# main.net
KiCad netlist of a schematic drawn in Altium Designer
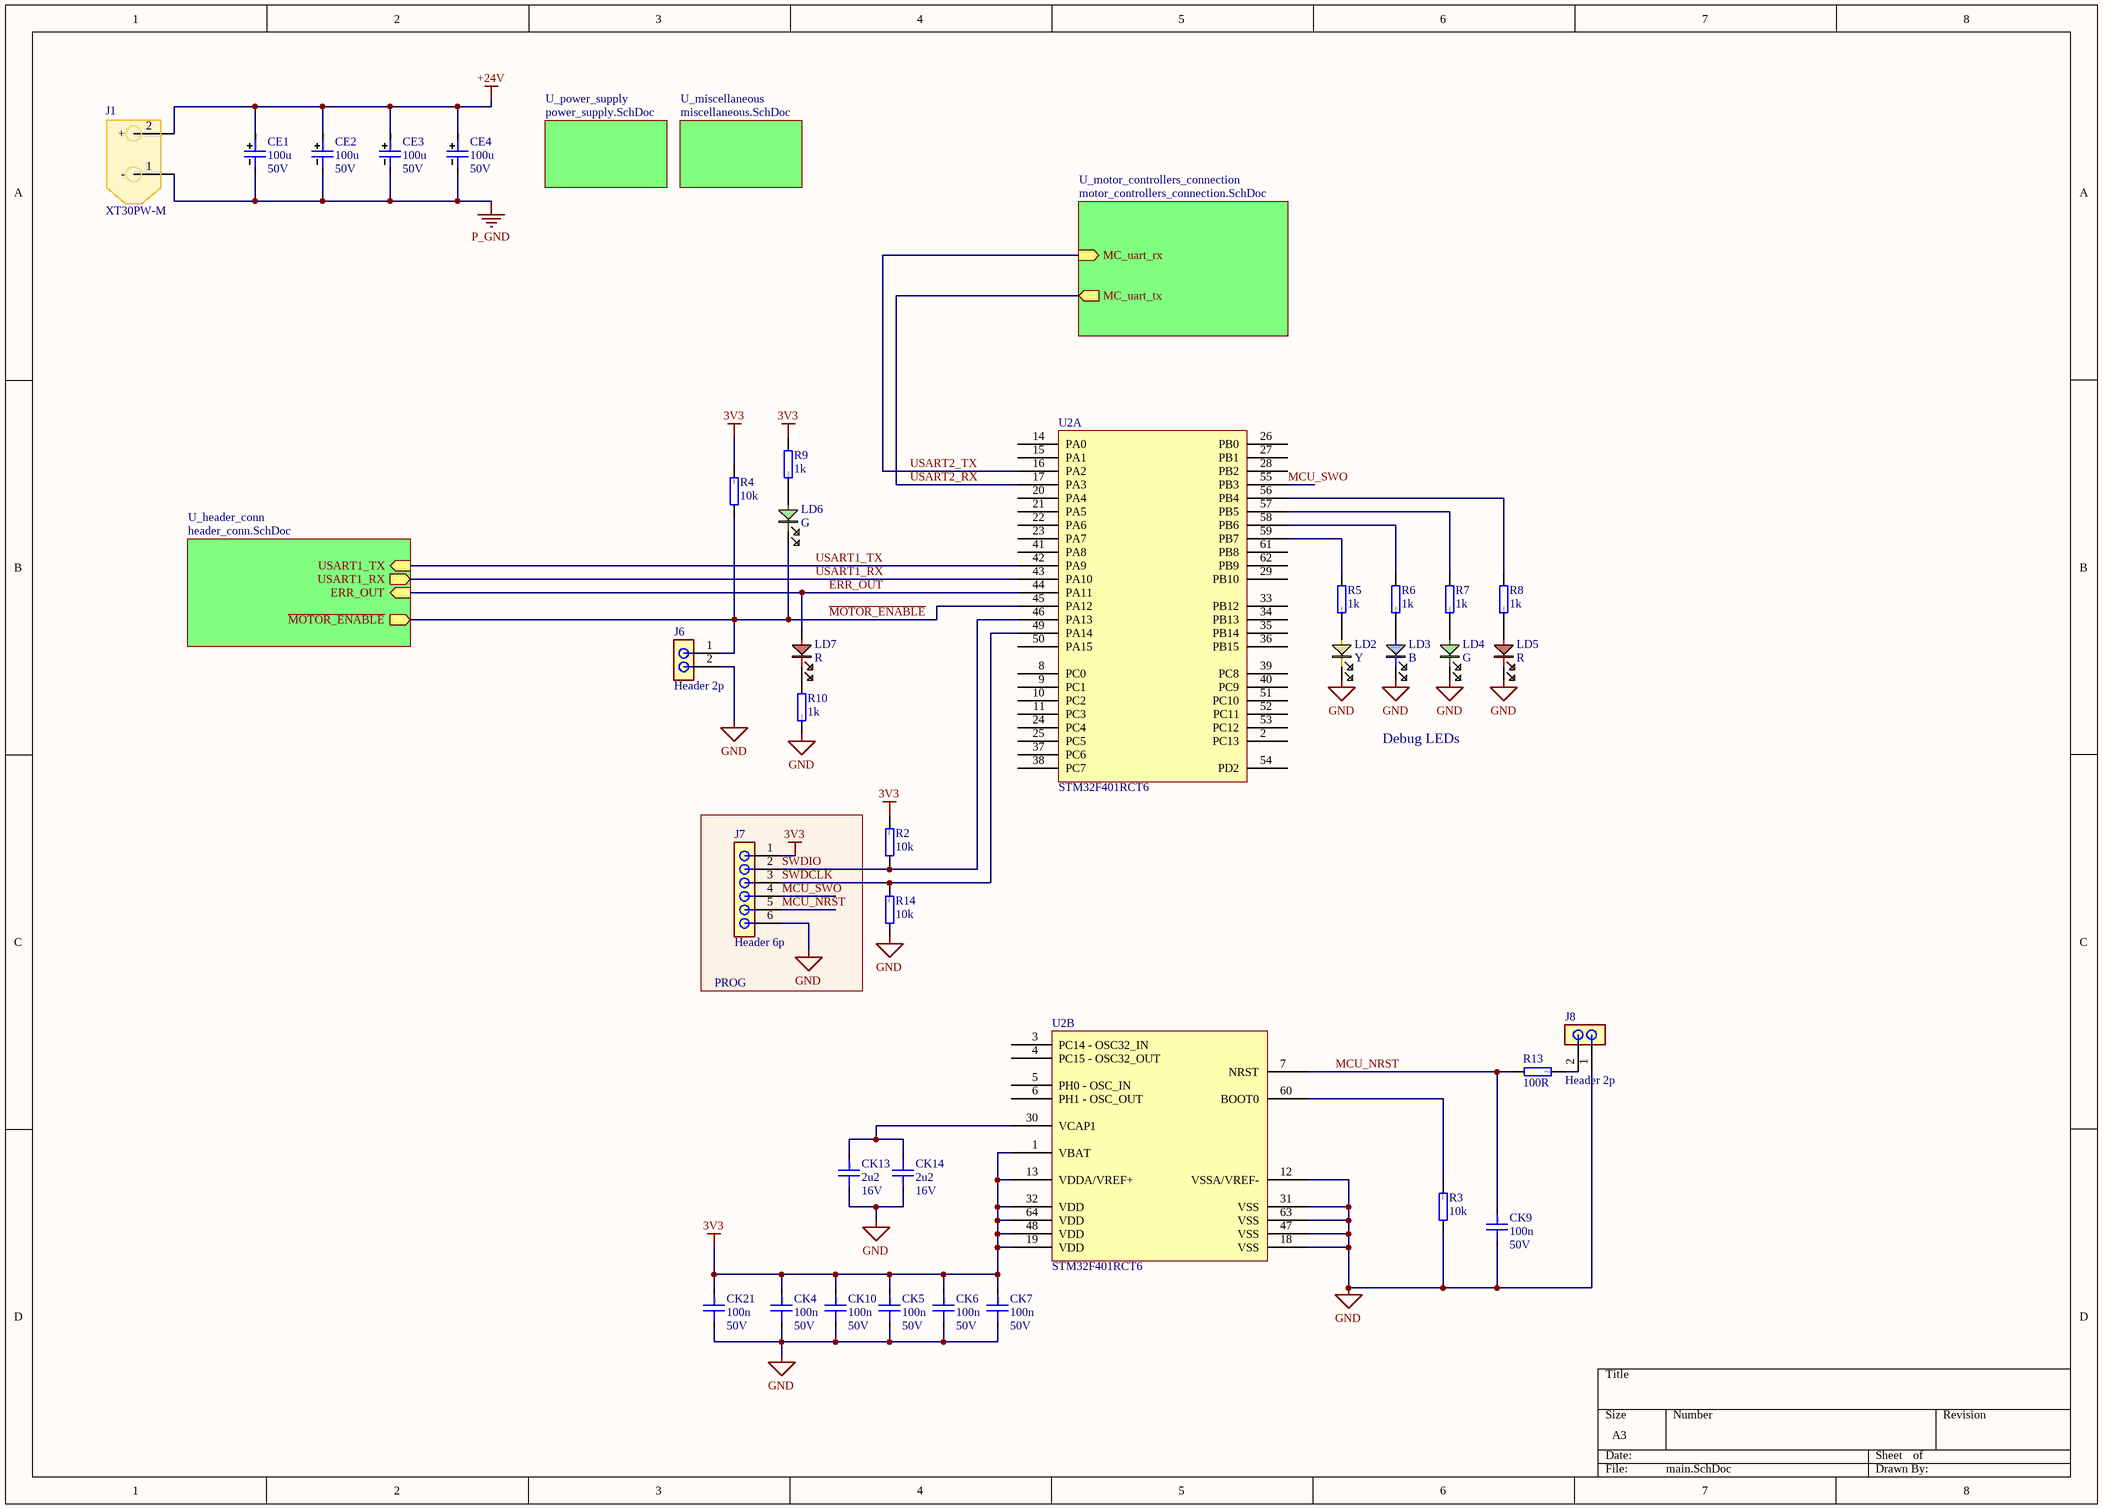
[diagram p0: main.SchDoc]

(export (version "E")
  (design (tool "Eeschema 10.0.6"))
  (components
    (comp (ref "CE1")
      (value "100u")
      (footprint "CAPAE830X1100N")
      (description "100uF 50V ±20% SMD,D8xL10.2mm Aluminum Electrolytic Capacitors - SMD ROHS")
      (fields
        (field (name "JLCPCB PART") "C3352")
        (field (name "TME PART") "CK1H107M08010VR")
        (field (name "VOLTAGE RATING") "50V")
      )
      (libsource (lib "Kubikova ultra knihovna") (part "Cap el 100u 50V"))
    )
    (comp (ref "CE2")
      (value "100u")
      (footprint "CAPAE830X1100N")
      (description "100uF 50V ±20% SMD,D8xL10.2mm Aluminum Electrolytic Capacitors - SMD ROHS")
      (fields
        (field (name "JLCPCB PART") "C3352")
        (field (name "TME PART") "CK1H107M08010VR")
        (field (name "VOLTAGE RATING") "50V")
      )
      (libsource (lib "Kubikova ultra knihovna") (part "Cap el 100u 50V"))
    )
    (comp (ref "CE3")
      (value "100u")
      (footprint "CAPAE830X1100N")
      (description "100uF 50V ±20% SMD,D8xL10.2mm Aluminum Electrolytic Capacitors - SMD ROHS")
      (fields
        (field (name "JLCPCB PART") "C3352")
        (field (name "TME PART") "CK1H107M08010VR")
        (field (name "VOLTAGE RATING") "50V")
      )
      (libsource (lib "Kubikova ultra knihovna") (part "Cap el 100u 50V"))
    )
    (comp (ref "CE4")
      (value "100u")
      (footprint "CAPAE830X1100N")
      (description "100uF 50V ±20% SMD,D8xL10.2mm Aluminum Electrolytic Capacitors - SMD ROHS")
      (fields
        (field (name "JLCPCB PART") "C3352")
        (field (name "TME PART") "CK1H107M08010VR")
        (field (name "VOLTAGE RATING") "50V")
      )
      (libsource (lib "Kubikova ultra knihovna") (part "Cap el 100u 50V"))
    )
    (comp (ref "CK4")
      (value "100n")
      (footprint "CAP0603")
      (description "50V 100nF X7R ±10% 0603 Multilayer Ceramic Capacitors MLCC - SMD/SMT ROHS")
      (fields (field (name "JLCPCB PART") "C14663") (field (name "VOLTAGE RATING") "50V"))
      (libsource (lib "Kubikova ultra knihovna") (part "Cap 100n 0603"))
    )
    (comp (ref "CK5")
      (value "100n")
      (footprint "CAP0603")
      (description "50V 100nF X7R ±10% 0603 Multilayer Ceramic Capacitors MLCC - SMD/SMT ROHS")
      (fields (field (name "JLCPCB PART") "C14663") (field (name "VOLTAGE RATING") "50V"))
      (libsource (lib "Kubikova ultra knihovna") (part "Cap 100n 0603"))
    )
    (comp (ref "CK6")
      (value "100n")
      (footprint "CAP0603")
      (description "50V 100nF X7R ±10% 0603 Multilayer Ceramic Capacitors MLCC - SMD/SMT ROHS")
      (fields (field (name "JLCPCB PART") "C14663") (field (name "VOLTAGE RATING") "50V"))
      (libsource (lib "Kubikova ultra knihovna") (part "Cap 100n 0603"))
    )
    (comp (ref "CK7")
      (value "100n")
      (footprint "CAP0603")
      (description "50V 100nF X7R ±10% 0603 Multilayer Ceramic Capacitors MLCC - SMD/SMT ROHS")
      (fields (field (name "JLCPCB PART") "C14663") (field (name "VOLTAGE RATING") "50V"))
      (libsource (lib "Kubikova ultra knihovna") (part "Cap 100n 0603"))
    )
    (comp (ref "CK9")
      (value "100n")
      (footprint "CAP0603")
      (description "50V 100nF X7R ±10% 0603 Multilayer Ceramic Capacitors MLCC - SMD/SMT ROHS")
      (fields (field (name "JLCPCB PART") "C14663") (field (name "VOLTAGE RATING") "50V"))
      (libsource (lib "Kubikova ultra knihovna") (part "Cap 100n 0603"))
    )
    (comp (ref "CK10")
      (value "100n")
      (footprint "CAP0603")
      (description "50V 100nF X7R ±10% 0603 Multilayer Ceramic Capacitors MLCC - SMD/SMT ROHS")
      (fields (field (name "JLCPCB PART") "C14663") (field (name "VOLTAGE RATING") "50V"))
      (libsource (lib "Kubikova ultra knihovna") (part "Cap 100n 0603"))
    )
    (comp (ref "CK13")
      (value "2u2")
      (footprint "CAP0603")
      (description "16V 2.2uF X5R ±10% 0603 Multilayer Ceramic Capacitors MLCC - SMD/SMT ROHS")
      (fields (field (name "JLCPCB PART") "C23630") (field (name "VOLTAGE RATING") "16V"))
      (libsource (lib "Kubikova ultra knihovna") (part "Cap 2u2 0603"))
    )
    (comp (ref "CK14")
      (value "2u2")
      (footprint "CAP0603")
      (description "16V 2.2uF X5R ±10% 0603 Multilayer Ceramic Capacitors MLCC - SMD/SMT ROHS")
      (fields (field (name "JLCPCB PART") "C23630") (field (name "VOLTAGE RATING") "16V"))
      (libsource (lib "Kubikova ultra knihovna") (part "Cap 2u2 0603"))
    )
    (comp (ref "CK21")
      (value "100n")
      (footprint "CAP0603")
      (description "50V 100nF X7R ±10% 0603 Multilayer Ceramic Capacitors MLCC - SMD/SMT ROHS")
      (fields (field (name "JLCPCB PART") "C14663") (field (name "VOLTAGE RATING") "50V"))
      (libsource (lib "Kubikova ultra knihovna") (part "Cap 100n 0603"))
    )
    (comp (ref "J1")
      (value "XT30PW-M")
      (footprint "XT30PWM")
      (description "plug")
      (fields (field (name "JLCPCB PART") "C431092"))
      (libsource (lib "Kubikova ultra knihovna") (part "XT30 male"))
    )
    (comp (ref "J6")
      (value "Header 2p")
      (footprint "Pin header 2p")
      (description "Connector")
      (fields
        (field (name "MANUFACTURER_PART_NUMBER") "DS1021-1*2SF11-B")
        (field (name "JLCPCB PART") "C492401")
      )
      (libsource (lib "Kubikova ultra knihovna") (part "Pin header 2p"))
    )
    (comp (ref "J7")
      (value "Header 6p")
      (footprint "Pin header 6p")
      (fields
        (field (name "MANUFACTURER_PART_NUMBER") "DS1021-1*2SF11-B")
        (field (name "JLCPCB PART") "C37208")
      )
      (libsource (lib "Kubikova ultra knihovna") (part "Pin header 6p"))
    )
    (comp (ref "J8")
      (value "Header 2p")
      (footprint "Pin header 2p")
      (description "Connector")
      (fields
        (field (name "MANUFACTURER_PART_NUMBER") "DS1021-1*2SF11-B")
        (field (name "JLCPCB PART") "C492401")
      )
      (libsource (lib "") (part "Pin header 2p_1"))
    )
    (comp (ref "LD2")
      (value "Y")
      (footprint "0603_LED_Y")
      (description "0603 Yellow Led")
      (fields (field (name "JLCPCB PART") "C7496811"))
      (libsource (lib "Kubikova ultra knihovna") (part "LED Y 0603"))
    )
    (comp (ref "LD3")
      (value "B")
      (footprint "0603_LED_B")
      (description "0603 Blue Led")
      (fields (field (name "JLCPCB PART") "C7496819"))
      (libsource (lib "Kubikova ultra knihovna") (part "LED B 0603"))
    )
    (comp (ref "LD4")
      (value "G")
      (footprint "0603_LED_G")
      (description "0603 Green Led")
      (fields (field (name "JLCPCB PART") "C22371297"))
      (libsource (lib "Kubikova ultra knihovna") (part "LED G 0603"))
    )
    (comp (ref "LD5")
      (value "R")
      (footprint "0603_LED_R")
      (description "-40℃~+85℃ Red 0603 LED Indication - Discrete ROHS")
      (fields (field (name "JLCPCB PART") "C2286"))
      (libsource (lib "Kubikova ultra knihovna") (part "LED R 0603"))
    )
    (comp (ref "LD6")
      (value "G")
      (footprint "0603_LED_G")
      (description "0603 Green Led")
      (fields (field (name "JLCPCB PART") "C22371297"))
      (libsource (lib "Kubikova ultra knihovna") (part "LED G 0603"))
    )
    (comp (ref "LD7")
      (value "R")
      (footprint "0603_LED_R")
      (description "-40℃~+85℃ Red 0603 LED Indication - Discrete ROHS")
      (fields (field (name "JLCPCB PART") "C2286"))
      (libsource (lib "Kubikova ultra knihovna") (part "LED R 0603"))
    )
    (comp (ref "R2")
      (value "10k")
      (footprint "RESC2012X06N(SMR0805)")
      (description "125mW Thick Film Resistors 150V ±100ppm/℃ ±1% 10kΩ 0805 Chip Resistor - Surface Mount ROHS")
      (fields (field (name "JLCPCB PART") "C17414"))
      (libsource (lib "Kubikova ultra knihovna") (part "Res 10k 0805"))
    )
    (comp (ref "R3")
      (value "10k")
      (footprint "RESC2012X06N(SMR0805)")
      (description "125mW Thick Film Resistors 150V ±100ppm/℃ ±1% 10kΩ 0805 Chip Resistor - Surface Mount ROHS")
      (fields (field (name "JLCPCB PART") "C17414"))
      (libsource (lib "Kubikova ultra knihovna") (part "Res 10k 0805"))
    )
    (comp (ref "R4")
      (value "10k")
      (footprint "RESC2012X06N(SMR0805)")
      (description "125mW Thick Film Resistors 150V ±100ppm/℃ ±1% 10kΩ 0805 Chip Resistor - Surface Mount ROHS")
      (fields (field (name "JLCPCB PART") "C17414"))
      (libsource (lib "Kubikova ultra knihovna") (part "Res 10k 0805"))
    )
    (comp (ref "R5")
      (value "1k")
      (footprint "RESC2012X06N(SMR0805)")
      (description "125mW Thick Film Resistors 150V ±100ppm/℃ ±1% 1kΩ 0805 Chip Resistor - Surface Mount ROHS")
      (fields (field (name "JLCPCB PART") "C17513") (field (name "AUTHOR") "JP/27.03.2014"))
      (libsource (lib "Kubikova ultra knihovna") (part "Res 1k 0805"))
    )
    (comp (ref "R6")
      (value "1k")
      (footprint "RESC2012X06N(SMR0805)")
      (description "125mW Thick Film Resistors 150V ±100ppm/℃ ±1% 1kΩ 0805 Chip Resistor - Surface Mount ROHS")
      (fields (field (name "JLCPCB PART") "C17513") (field (name "AUTHOR") "JP/27.03.2014"))
      (libsource (lib "Kubikova ultra knihovna") (part "Res 1k 0805"))
    )
    (comp (ref "R7")
      (value "1k")
      (footprint "RESC2012X06N(SMR0805)")
      (description "125mW Thick Film Resistors 150V ±100ppm/℃ ±1% 1kΩ 0805 Chip Resistor - Surface Mount ROHS")
      (fields (field (name "JLCPCB PART") "C17513") (field (name "AUTHOR") "JP/27.03.2014"))
      (libsource (lib "Kubikova ultra knihovna") (part "Res 1k 0805"))
    )
    (comp (ref "R8")
      (value "1k")
      (footprint "RESC2012X06N(SMR0805)")
      (description "125mW Thick Film Resistors 150V ±100ppm/℃ ±1% 1kΩ 0805 Chip Resistor - Surface Mount ROHS")
      (fields (field (name "JLCPCB PART") "C17513") (field (name "AUTHOR") "JP/27.03.2014"))
      (libsource (lib "Kubikova ultra knihovna") (part "Res 1k 0805"))
    )
    (comp (ref "R9")
      (value "1k")
      (footprint "RESC2012X06N(SMR0805)")
      (description "125mW Thick Film Resistors 150V ±100ppm/℃ ±1% 1kΩ 0805 Chip Resistor - Surface Mount ROHS")
      (fields (field (name "JLCPCB PART") "C17513") (field (name "AUTHOR") "JP/27.03.2014"))
      (libsource (lib "Kubikova ultra knihovna") (part "Res 1k 0805"))
    )
    (comp (ref "R10")
      (value "1k")
      (footprint "RESC2012X06N(SMR0805)")
      (description "125mW Thick Film Resistors 150V ±100ppm/℃ ±1% 1kΩ 0805 Chip Resistor - Surface Mount ROHS")
      (fields (field (name "JLCPCB PART") "C17513") (field (name "AUTHOR") "JP/27.03.2014"))
      (libsource (lib "Kubikova ultra knihovna") (part "Res 1k 0805"))
    )
    (comp (ref "R13")
      (value "100R")
      (footprint "RESC2012X06N(SMR0805)")
      (description "125mW Thick Film Resistors 150V ±100ppm/℃ ±1% 100Ω 0805 Chip Resistor - Surface Mount ROHS")
      (fields (field (name "JLCPCB PART") "C17408") (field (name "AUTHOR") "JP/27.03.2014"))
      (libsource (lib "Kubikova ultra knihovna") (part "Res 100R 0805"))
    )
    (comp (ref "R14")
      (value "10k")
      (footprint "RESC2012X06N(SMR0805)")
      (description "125mW Thick Film Resistors 150V ±100ppm/℃ ±1% 10kΩ 0805 Chip Resistor - Surface Mount ROHS")
      (fields (field (name "JLCPCB PART") "C17414"))
      (libsource (lib "Kubikova ultra knihovna") (part "Res 10k 0805"))
    )
    (comp (ref "U2")
      (value "STM32F401RCT6")
      (footprint "LQFP64")
      (description "256KB 1.7V~3.6V ARM-M4 64KB 84MHz FLASH 50 LQFP-64(10x10) Microcontrollers (MCU/MPU/SOC) ROHS")
      (fields (field (name "JLCPCB PART") "C74524"))
      (libsource (lib "Kubikova ultra knihovna") (part "STM32F401RCT6"))
    )
  )
  (nets
    (net (code "1") (name "+24V") (class "Default")
      (node (ref "CE1") (pin "1") (pinfunction "1_1") (pintype "passive"))
      (node (ref "CE2") (pin "1") (pinfunction "1_1") (pintype "passive"))
      (node (ref "CE3") (pin "1") (pinfunction "1_1") (pintype "passive"))
      (node (ref "CE4") (pin "1") (pinfunction "1_1") (pintype "passive"))
      (node (ref "J1") (pin "2") (pinfunction "+_2") (pintype "passive"))
    )
    (net (code "2") (name "/ERR_OUT") (class "Default")
      (node (ref "LD7") (pin "1") (pintype "passive"))
      (node (ref "U2") (pin "44") (pinfunction "PA11_44") (pintype "passive"))
    )
    (net (code "3") (name "/MCU_NRST") (class "Default")
      (node (ref "CK9") (pin "1") (pinfunction "1_1") (pintype "passive"))
      (node (ref "J7") (pin "5") (pinfunction "5_5") (pintype "passive"))
      (node (ref "R13") (pin "1") (pinfunction "1_1") (pintype "passive"))
      (node (ref "U2") (pin "7") (pinfunction "NRST_7") (pintype "passive"))
    )
    (net (code "4") (name "/MCU_SWO") (class "Default")
      (node (ref "J7") (pin "4") (pinfunction "4_4") (pintype "passive"))
      (node (ref "U2") (pin "55") (pinfunction "PB3_55") (pintype "passive"))
    )
    (net (code "5") (name "/SWDCLK") (class "Default")
      (node (ref "J7") (pin "3") (pinfunction "3_3") (pintype "passive"))
      (node (ref "R14") (pin "2") (pinfunction "2_2") (pintype "passive"))
      (node (ref "U2") (pin "49") (pinfunction "PA14_49") (pintype "passive"))
    )
    (net (code "6") (name "/SWDIO") (class "Default")
      (node (ref "J7") (pin "2") (pinfunction "2_2") (pintype "passive"))
      (node (ref "R2") (pin "1") (pinfunction "1_1") (pintype "passive"))
      (node (ref "U2") (pin "46") (pinfunction "PA13_46") (pintype "passive"))
    )
    (net (code "7") (name "/USART1_RX") (class "Default")
      (node (ref "U2") (pin "43") (pinfunction "PA10_43") (pintype "passive"))
    )
    (net (code "8") (name "/USART1_TX") (class "Default")
      (node (ref "U2") (pin "42") (pinfunction "PA9_42") (pintype "passive"))
    )
    (net (code "9") (name "/USART2_RX") (class "Default")
      (node (ref "U2") (pin "17") (pinfunction "PA3_17") (pintype "passive"))
    )
    (net (code "10") (name "/USART2_TX") (class "Default")
      (node (ref "U2") (pin "16") (pinfunction "PA2_16") (pintype "passive"))
    )
    (net (code "11") (name "/~{MOTOR_ENABLE}") (class "Default")
      (node (ref "J6") (pin "1") (pinfunction "1_1") (pintype "passive"))
      (node (ref "LD6") (pin "2") (pintype "passive"))
      (node (ref "R4") (pin "1") (pinfunction "1_1") (pintype "passive"))
      (node (ref "U2") (pin "45") (pinfunction "PA12_45") (pintype "passive"))
    )
    (net (code "12") (name "3V3") (class "Default")
      (node (ref "CK10") (pin "1") (pinfunction "1_1") (pintype "passive"))
      (node (ref "CK21") (pin "1") (pinfunction "1_1") (pintype "passive"))
      (node (ref "CK4") (pin "1") (pinfunction "1_1") (pintype "passive"))
      (node (ref "CK5") (pin "1") (pinfunction "1_1") (pintype "passive"))
      (node (ref "CK6") (pin "1") (pinfunction "1_1") (pintype "passive"))
      (node (ref "CK7") (pin "1") (pinfunction "1_1") (pintype "passive"))
      (node (ref "J7") (pin "1") (pinfunction "1_1") (pintype "passive"))
      (node (ref "R2") (pin "2") (pinfunction "2_2") (pintype "passive"))
      (node (ref "R4") (pin "2") (pinfunction "2_2") (pintype "passive"))
      (node (ref "R9") (pin "1") (pinfunction "1_1") (pintype "passive"))
      (node (ref "U2") (pin "1") (pinfunction "VBAT_1") (pintype "passive"))
      (node (ref "U2") (pin "13") (pinfunction "VDDA/VREF+_13") (pintype "passive"))
      (node (ref "U2") (pin "19") (pinfunction "VDD_19") (pintype "passive"))
      (node (ref "U2") (pin "32") (pinfunction "VDD_32") (pintype "passive"))
      (node (ref "U2") (pin "48") (pinfunction "VDD_48") (pintype "passive"))
      (node (ref "U2") (pin "64") (pinfunction "VDD_64") (pintype "passive"))
    )
    (net (code "13") (name "GND") (class "Default")
      (node (ref "CK10") (pin "2") (pinfunction "2_2") (pintype "passive"))
      (node (ref "CK13") (pin "2") (pinfunction "2_2") (pintype "passive"))
      (node (ref "CK14") (pin "1") (pinfunction "1_1") (pintype "passive"))
      (node (ref "CK21") (pin "2") (pinfunction "2_2") (pintype "passive"))
      (node (ref "CK4") (pin "2") (pinfunction "2_2") (pintype "passive"))
      (node (ref "CK5") (pin "2") (pinfunction "2_2") (pintype "passive"))
      (node (ref "CK6") (pin "2") (pinfunction "2_2") (pintype "passive"))
      (node (ref "CK7") (pin "2") (pinfunction "2_2") (pintype "passive"))
      (node (ref "CK9") (pin "2") (pinfunction "2_2") (pintype "passive"))
      (node (ref "J6") (pin "2") (pinfunction "2_2") (pintype "passive"))
      (node (ref "J7") (pin "6") (pinfunction "6_6") (pintype "passive"))
      (node (ref "J8") (pin "1") (pinfunction "1_1") (pintype "passive"))
      (node (ref "LD2") (pin "2") (pintype "passive"))
      (node (ref "LD3") (pin "2") (pintype "passive"))
      (node (ref "LD4") (pin "2") (pintype "passive"))
      (node (ref "LD5") (pin "2") (pintype "passive"))
      (node (ref "R10") (pin "2") (pinfunction "2_2") (pintype "passive"))
      (node (ref "R14") (pin "1") (pinfunction "1_1") (pintype "passive"))
      (node (ref "R3") (pin "1") (pinfunction "1_1") (pintype "passive"))
      (node (ref "U2") (pin "12") (pinfunction "VSSA/VREF-_12") (pintype "passive"))
      (node (ref "U2") (pin "18") (pinfunction "VSS_18") (pintype "passive"))
      (node (ref "U2") (pin "31") (pinfunction "VSS_31") (pintype "passive"))
      (node (ref "U2") (pin "47") (pinfunction "VSS_47") (pintype "passive"))
      (node (ref "U2") (pin "63") (pinfunction "VSS_63") (pintype "passive"))
    )
    (net (code "14") (name "Net-(J8-Pad2)") (class "Default")
      (node (ref "J8") (pin "2") (pinfunction "2_2") (pintype "passive"))
      (node (ref "R13") (pin "2") (pinfunction "2_2") (pintype "passive"))
    )
    (net (code "15") (name "Net-(LD2-Pad1)") (class "Default")
      (node (ref "LD2") (pin "1") (pintype "passive"))
      (node (ref "R5") (pin "2") (pinfunction "2_2") (pintype "passive"))
    )
    (net (code "16") (name "Net-(LD3-Pad1)") (class "Default")
      (node (ref "LD3") (pin "1") (pintype "passive"))
      (node (ref "R6") (pin "2") (pinfunction "2_2") (pintype "passive"))
    )
    (net (code "17") (name "Net-(LD4-Pad1)") (class "Default")
      (node (ref "LD4") (pin "1") (pintype "passive"))
      (node (ref "R7") (pin "2") (pinfunction "2_2") (pintype "passive"))
    )
    (net (code "18") (name "Net-(LD5-Pad1)") (class "Default")
      (node (ref "LD5") (pin "1") (pintype "passive"))
      (node (ref "R8") (pin "2") (pinfunction "2_2") (pintype "passive"))
    )
    (net (code "19") (name "Net-(LD6-Pad1)") (class "Default")
      (node (ref "LD6") (pin "1") (pintype "passive"))
      (node (ref "R9") (pin "2") (pinfunction "2_2") (pintype "passive"))
    )
    (net (code "20") (name "Net-(LD7-Pad2)") (class "Default")
      (node (ref "LD7") (pin "2") (pintype "passive"))
      (node (ref "R10") (pin "1") (pinfunction "1_1") (pintype "passive"))
    )
    (net (code "21") (name "Net-(U2A-PB4)") (class "Default")
      (node (ref "R8") (pin "1") (pinfunction "1_1") (pintype "passive"))
      (node (ref "U2") (pin "56") (pinfunction "PB4_56") (pintype "passive"))
    )
    (net (code "22") (name "Net-(U2A-PB5)") (class "Default")
      (node (ref "R7") (pin "1") (pinfunction "1_1") (pintype "passive"))
      (node (ref "U2") (pin "57") (pinfunction "PB5_57") (pintype "passive"))
    )
    (net (code "23") (name "Net-(U2A-PB6)") (class "Default")
      (node (ref "R6") (pin "1") (pinfunction "1_1") (pintype "passive"))
      (node (ref "U2") (pin "58") (pinfunction "PB6_58") (pintype "passive"))
    )
    (net (code "24") (name "Net-(U2A-PB7)") (class "Default")
      (node (ref "R5") (pin "1") (pinfunction "1_1") (pintype "passive"))
      (node (ref "U2") (pin "59") (pinfunction "PB7_59") (pintype "passive"))
    )
    (net (code "25") (name "Net-(U2B-BOOT0)") (class "Default")
      (node (ref "R3") (pin "2") (pinfunction "2_2") (pintype "passive"))
      (node (ref "U2") (pin "60") (pinfunction "BOOT0_60") (pintype "passive"))
    )
    (net (code "26") (name "Net-(U2B-VCAP1)") (class "Default")
      (node (ref "CK13") (pin "1") (pinfunction "1_1") (pintype "passive"))
      (node (ref "CK14") (pin "2") (pinfunction "2_2") (pintype "passive"))
      (node (ref "U2") (pin "30") (pinfunction "VCAP1_30") (pintype "passive"))
    )
    (net (code "27") (name "P_GND") (class "Default")
      (node (ref "CE1") (pin "2") (pinfunction "2_2") (pintype "passive"))
      (node (ref "CE2") (pin "2") (pinfunction "2_2") (pintype "passive"))
      (node (ref "CE3") (pin "2") (pinfunction "2_2") (pintype "passive"))
      (node (ref "CE4") (pin "2") (pinfunction "2_2") (pintype "passive"))
      (node (ref "J1") (pin "1") (pinfunction "-_1") (pintype "passive"))
    )
    (net (code "28") (name "unconnected-(U2A-PA0-Pad14)") (class "Default")
      (node (ref "U2") (pin "14") (pinfunction "PA0_14") (pintype "passive"))
    )
    (net (code "29") (name "unconnected-(U2A-PA1-Pad15)") (class "Default")
      (node (ref "U2") (pin "15") (pinfunction "PA1_15") (pintype "passive"))
    )
    (net (code "30") (name "unconnected-(U2A-PA4-Pad20)") (class "Default")
      (node (ref "U2") (pin "20") (pinfunction "PA4_20") (pintype "passive"))
    )
    (net (code "31") (name "unconnected-(U2A-PA5-Pad21)") (class "Default")
      (node (ref "U2") (pin "21") (pinfunction "PA5_21") (pintype "passive"))
    )
    (net (code "32") (name "unconnected-(U2A-PA6-Pad22)") (class "Default")
      (node (ref "U2") (pin "22") (pinfunction "PA6_22") (pintype "passive"))
    )
    (net (code "33") (name "unconnected-(U2A-PA7-Pad23)") (class "Default")
      (node (ref "U2") (pin "23") (pinfunction "PA7_23") (pintype "passive"))
    )
    (net (code "34") (name "unconnected-(U2A-PA8-Pad41)") (class "Default")
      (node (ref "U2") (pin "41") (pinfunction "PA8_41") (pintype "passive"))
    )
    (net (code "35") (name "unconnected-(U2A-PA15-Pad50)") (class "Default")
      (node (ref "U2") (pin "50") (pinfunction "PA15_50") (pintype "passive"))
    )
    (net (code "36") (name "unconnected-(U2A-PB0-Pad26)") (class "Default")
      (node (ref "U2") (pin "26") (pinfunction "PB0_26") (pintype "passive"))
    )
    (net (code "37") (name "unconnected-(U2A-PB1-Pad27)") (class "Default")
      (node (ref "U2") (pin "27") (pinfunction "PB1_27") (pintype "passive"))
    )
    (net (code "38") (name "unconnected-(U2A-PB2-Pad28)") (class "Default")
      (node (ref "U2") (pin "28") (pinfunction "PB2_28") (pintype "passive"))
    )
    (net (code "39") (name "unconnected-(U2A-PB8-Pad61)") (class "Default")
      (node (ref "U2") (pin "61") (pinfunction "PB8_61") (pintype "passive"))
    )
    (net (code "40") (name "unconnected-(U2A-PB9-Pad62)") (class "Default")
      (node (ref "U2") (pin "62") (pinfunction "PB9_62") (pintype "passive"))
    )
    (net (code "41") (name "unconnected-(U2A-PB10-Pad29)") (class "Default")
      (node (ref "U2") (pin "29") (pinfunction "PB10_29") (pintype "passive"))
    )
    (net (code "42") (name "unconnected-(U2A-PB12-Pad33)") (class "Default")
      (node (ref "U2") (pin "33") (pinfunction "PB12_33") (pintype "passive"))
    )
    (net (code "43") (name "unconnected-(U2A-PB13-Pad34)") (class "Default")
      (node (ref "U2") (pin "34") (pinfunction "PB13_34") (pintype "passive"))
    )
    (net (code "44") (name "unconnected-(U2A-PB14-Pad35)") (class "Default")
      (node (ref "U2") (pin "35") (pinfunction "PB14_35") (pintype "passive"))
    )
    (net (code "45") (name "unconnected-(U2A-PB15-Pad36)") (class "Default")
      (node (ref "U2") (pin "36") (pinfunction "PB15_36") (pintype "passive"))
    )
    (net (code "46") (name "unconnected-(U2A-PC0-Pad8)") (class "Default")
      (node (ref "U2") (pin "8") (pinfunction "PC0_8") (pintype "passive"))
    )
    (net (code "47") (name "unconnected-(U2A-PC1-Pad9)") (class "Default")
      (node (ref "U2") (pin "9") (pinfunction "PC1_9") (pintype "passive"))
    )
    (net (code "48") (name "unconnected-(U2A-PC2-Pad10)") (class "Default")
      (node (ref "U2") (pin "10") (pinfunction "PC2_10") (pintype "passive"))
    )
    (net (code "49") (name "unconnected-(U2A-PC3-Pad11)") (class "Default")
      (node (ref "U2") (pin "11") (pinfunction "PC3_11") (pintype "passive"))
    )
    (net (code "50") (name "unconnected-(U2A-PC4-Pad24)") (class "Default")
      (node (ref "U2") (pin "24") (pinfunction "PC4_24") (pintype "passive"))
    )
    (net (code "51") (name "unconnected-(U2A-PC5-Pad25)") (class "Default")
      (node (ref "U2") (pin "25") (pinfunction "PC5_25") (pintype "passive"))
    )
    (net (code "52") (name "unconnected-(U2A-PC6-Pad37)") (class "Default")
      (node (ref "U2") (pin "37") (pinfunction "PC6_37") (pintype "passive"))
    )
    (net (code "53") (name "unconnected-(U2A-PC7-Pad38)") (class "Default")
      (node (ref "U2") (pin "38") (pinfunction "PC7_38") (pintype "passive"))
    )
    (net (code "54") (name "unconnected-(U2A-PC8-Pad39)") (class "Default")
      (node (ref "U2") (pin "39") (pinfunction "PC8_39") (pintype "passive"))
    )
    (net (code "55") (name "unconnected-(U2A-PC9-Pad40)") (class "Default")
      (node (ref "U2") (pin "40") (pinfunction "PC9_40") (pintype "passive"))
    )
    (net (code "56") (name "unconnected-(U2A-PC10-Pad51)") (class "Default")
      (node (ref "U2") (pin "51") (pinfunction "PC10_51") (pintype "passive"))
    )
    (net (code "57") (name "unconnected-(U2A-PC11-Pad52)") (class "Default")
      (node (ref "U2") (pin "52") (pinfunction "PC11_52") (pintype "passive"))
    )
    (net (code "58") (name "unconnected-(U2A-PC12-Pad53)") (class "Default")
      (node (ref "U2") (pin "53") (pinfunction "PC12_53") (pintype "passive"))
    )
    (net (code "59") (name "unconnected-(U2A-PC13-Pad2)") (class "Default")
      (node (ref "U2") (pin "2") (pinfunction "PC13_2") (pintype "passive"))
    )
    (net (code "60") (name "unconnected-(U2A-PD2-Pad54)") (class "Default")
      (node (ref "U2") (pin "54") (pinfunction "PD2_54") (pintype "passive"))
    )
    (net (code "61") (name "unconnected-(U2B-PC14_-_OSC32_IN-Pad3)") (class "Default")
      (node (ref "U2") (pin "3") (pinfunction "PC14_-_OSC32_IN_3") (pintype "passive"))
    )
    (net (code "62") (name "unconnected-(U2B-PC15_-_OSC32_OUT-Pad4)") (class "Default")
      (node (ref "U2") (pin "4") (pinfunction "PC15_-_OSC32_OUT_4") (pintype "passive"))
    )
    (net (code "63") (name "unconnected-(U2B-PH0_-_OSC_IN-Pad5)") (class "Default")
      (node (ref "U2") (pin "5") (pinfunction "PH0_-_OSC_IN_5") (pintype "passive"))
    )
    (net (code "64") (name "unconnected-(U2B-PH1_-_OSC_OUT-Pad6)") (class "Default")
      (node (ref "U2") (pin "6") (pinfunction "PH1_-_OSC_OUT_6") (pintype "passive"))
    )
  )
)
